# CIBLE_Main.net
KiCad netlist of a schematic drawn in Altium Designer
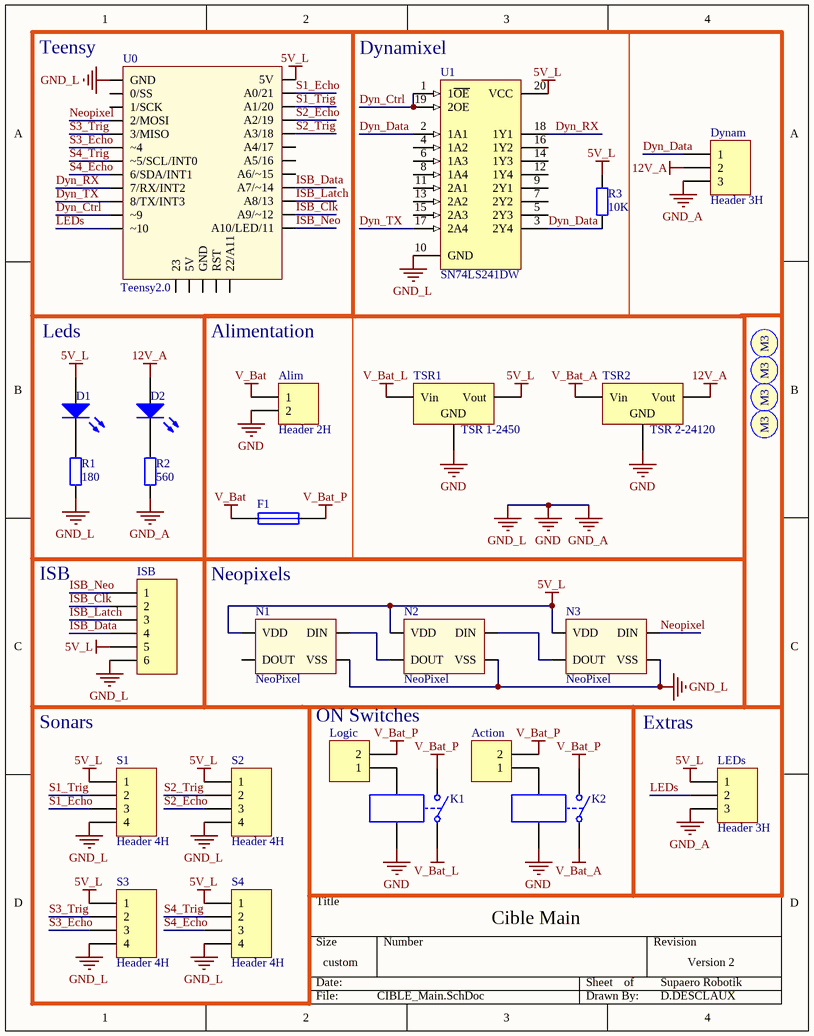
[diagram p0: CIBLE_Main.SchDoc]

(export (version "E")
  (design (tool "Eeschema 10.0.6"))
  (components
    (comp (ref "Action")
      (value "Action")
      (footprint "Molex SPOX 2x1H")
      (description "Header, 2-Pin, Right Angle")
      (fields (field (name "PUBLISHER") "Altium Limited"))
      (libsource (lib "Miscellaneous Connectors") (part "Header 2H"))
    )
    (comp (ref "Alim")
      (value "Header 2H")
      (footprint "Battery SALE")
      (description "Header, 2-Pin, Right Angle")
      (fields (field (name "PUBLISHER") "Altium Limited"))
      (libsource (lib "") (part "Header 2H_1"))
    )
    (comp (ref "D1")
      (value "KP-3216SEC")
      (footprint "3.2X1.6X1.1")
      (description "Typical RED, GREEN, YELLOW, AMBER GaAs LED")
      (fields (field (name "PUBLISHER") "Altium Limited"))
      (libsource (lib "Miscellaneous Devices") (part "LED2"))
    )
    (comp (ref "D2")
      (value "KP-3216SEC")
      (footprint "3.2X1.6X1.1")
      (description "Typical RED, GREEN, YELLOW, AMBER GaAs LED")
      (fields (field (name "PUBLISHER") "Altium Limited"))
      (libsource (lib "Miscellaneous Devices") (part "LED2"))
    )
    (comp (ref "Dynam")
      (value "Header 3H")
      (footprint "Molex SPOX 3x1H")
      (description "Header, 3-Pin, Right Angle")
      (fields (field (name "PUBLISHER") "Altium Limited"))
      (libsource (lib "Miscellaneous Connectors") (part "Header 3H"))
    )
    (comp (ref "F1")
      (value "Fuse 1")
      (footprint "Fuse")
      (description "Fuse")
      (fields (field (name "PUBLISHER") "Altium Limited"))
      (libsource (lib "Miscellaneous Devices") (part "Fuse 1"))
    )
    (comp (ref "ISB")
      (value "Header 6H")
      (footprint "MOLEX SPOX 6X1H")
      (description "Header, 6-Pin, Right Angle")
      (fields (field (name "PUBLISHER") "Altium Limited"))
      (libsource (lib "Miscellaneous Connectors") (part "Header 6H"))
    )
    (comp (ref "K1")
      (value "OJ-SS-112LMH2")
      (footprint "Relay")
      (description "Single-Pole Single-Throw Relay")
      (fields (field (name "PUBLISHER") "Altium Limited"))
      (libsource (lib "Miscellaneous Devices") (part "Relay-SPST"))
    )
    (comp (ref "K2")
      (value "OJ-SS-112LMH2")
      (footprint "Relay")
      (description "Single-Pole Single-Throw Relay")
      (fields (field (name "PUBLISHER") "Altium Limited"))
      (libsource (lib "Miscellaneous Devices") (part "Relay-SPST"))
    )
    (comp (ref "LEDs")
      (value "Header 3H")
      (footprint "Molex SPOX 3x1H")
      (description "Header, 3-Pin, Right Angle")
      (fields (field (name "PUBLISHER") "Altium Limited"))
      (libsource (lib "Miscellaneous Connectors") (part "Header 3H"))
    )
    (comp (ref "Logic")
      (value "Logic")
      (footprint "Molex SPOX 2x1H")
      (description "Header, 2-Pin, Right Angle")
      (fields (field (name "PUBLISHER") "Altium Limited"))
      (libsource (lib "Miscellaneous Connectors") (part "Header 2H"))
    )
    (comp (ref "N1")
      (value "NeoPixel")
      (footprint "Robot_2019:Neopixel")
      (libsource (lib "Robot_2019") (part "NeoPixel"))
    )
    (comp (ref "N2")
      (value "NeoPixel")
      (footprint "Robot_2019:Neopixel")
      (libsource (lib "Robot_2019") (part "NeoPixel"))
    )
    (comp (ref "N3")
      (value "NeoPixel")
      (footprint "Robot_2019:Neopixel")
      (libsource (lib "Robot_2019") (part "NeoPixel"))
    )
    (comp (ref "R1")
      (value "180")
      (footprint "3.2X1.6X1.1")
      (description "Resistor")
      (fields (field (name "Comment") "Res2") (field (name "PUBLISHER") "Altium Limited"))
      (libsource (lib "Miscellaneous Devices") (part "Res2"))
    )
    (comp (ref "R2")
      (value "560")
      (footprint "3.2X1.6X1.1")
      (description "Resistor")
      (fields (field (name "Comment") "Res2") (field (name "PUBLISHER") "Altium Limited"))
      (libsource (lib "Miscellaneous Devices") (part "Res2"))
    )
    (comp (ref "R3")
      (value "10K")
      (footprint "3.2X1.6X1.1")
      (description "Resistor")
      (fields (field (name "Comment") "Res2") (field (name "PUBLISHER") "Altium Limited"))
      (libsource (lib "") (part "Res2_1"))
    )
    (comp (ref "S1")
      (value "Header 4H")
      (footprint "Molex SPOX 4x1H")
      (description "Header, 4-Pin, Right Angle")
      (fields (field (name "PUBLISHER") "Altium Limited"))
      (libsource (lib "Miscellaneous Connectors") (part "Header 4H"))
    )
    (comp (ref "S2")
      (value "Header 4H")
      (footprint "Molex SPOX 4x1H")
      (description "Header, 4-Pin, Right Angle")
      (fields (field (name "PUBLISHER") "Altium Limited"))
      (libsource (lib "Miscellaneous Connectors") (part "Header 4H"))
    )
    (comp (ref "S3")
      (value "Header 4H")
      (footprint "Molex SPOX 4x1H")
      (description "Header, 4-Pin, Right Angle")
      (fields (field (name "PUBLISHER") "Altium Limited"))
      (libsource (lib "Miscellaneous Connectors") (part "Header 4H"))
    )
    (comp (ref "S4")
      (value "Header 4H")
      (footprint "Molex SPOX 4x1H")
      (description "Header, 4-Pin, Right Angle")
      (fields (field (name "PUBLISHER") "Altium Limited"))
      (libsource (lib "Miscellaneous Connectors") (part "Header 4H"))
    )
    (comp (ref "SC1")
      (value "Screw M3")
      (footprint "Robot_2019:Screw M3")
      (libsource (lib "Robot_2019") (part "Screw M3"))
    )
    (comp (ref "SC2")
      (value "Screw M3")
      (footprint "Robot_2019:Screw M3")
      (libsource (lib "Robot_2019") (part "Screw M3"))
    )
    (comp (ref "SC3")
      (value "Screw M3")
      (footprint "Robot_2019:Screw M3")
      (libsource (lib "Robot_2019") (part "Screw M3"))
    )
    (comp (ref "SC4")
      (value "Screw M3")
      (footprint "Robot_2019:Screw M3")
      (libsource (lib "Robot_2019") (part "Screw M3"))
    )
    (comp (ref "TSR1")
      (value "TSR 1-2450")
      (footprint "TRS")
      (description "Voltage Regulator")
      (fields (field (name "PUBLISHER") "Altium Limited"))
      (libsource (lib "Miscellaneous Devices") (part "Volt Reg"))
    )
    (comp (ref "TSR2")
      (value "TSR 2-24120")
      (footprint "TRS - centered")
      (description "Voltage Regulator")
      (fields (field (name "PUBLISHER") "Altium Limited"))
      (libsource (lib "Miscellaneous Devices") (part "Volt Reg"))
    )
    (comp (ref "U0")
      (value "Teensy2.0")
      (footprint "Teensy2.0")
      (description "Teensy 2.0 with minimal pinout")
      (libsource (lib "Robot_2019") (part "Teensy2.0"))
    )
    (comp (ref "U1")
      (value "SN74LS241DW")
      (footprint "DW020_N")
      (description "Octal Buffer and Line Driver with 3-State Outputs")
      (fields (field (name "PUBLISHER") "Altium Limited"))
      (libsource (lib "TI Logic Buffer Line Driver") (part "SN74LS241DW"))
    )
  )
  (nets
    (net (code "1") (name "/Dyn_Ctrl") (class "Default")
      (node (ref "U0") (pin "11") (pinfunction "~9_11") (pintype "passive"))
      (node (ref "U1") (pin "1") (pinfunction "1~{OE}_1") (pintype "input"))
      (node (ref "U1") (pin "19") (pinfunction "2OE_19") (pintype "input"))
    )
    (net (code "2") (name "/Dyn_Data") (class "Default")
      (node (ref "Dynam") (pin "1") (pinfunction "1_1") (pintype "passive"))
      (node (ref "R3") (pin "1") (pinfunction "1_1") (pintype "passive"))
      (node (ref "U1") (pin "2") (pinfunction "1A1_2") (pintype "input"))
      (node (ref "U1") (pin "3") (pinfunction "2Y4_3") (pintype "tri_state"))
    )
    (net (code "3") (name "/Dyn_RX") (class "Default")
      (node (ref "U0") (pin "9") (pinfunction "7/RX/INT2_9") (pintype "passive"))
      (node (ref "U1") (pin "18") (pinfunction "1Y1_18") (pintype "tri_state"))
    )
    (net (code "4") (name "/Dyn_TX") (class "Default")
      (node (ref "U0") (pin "10") (pinfunction "8/TX/INT3_10") (pintype "passive"))
      (node (ref "U1") (pin "17") (pinfunction "2A4_17") (pintype "input"))
    )
    (net (code "5") (name "/ISB_Clk") (class "Default")
      (node (ref "ISB") (pin "2") (pinfunction "2_2") (pintype "passive"))
      (node (ref "U0") (pin "19") (pinfunction "A9/~12_19") (pintype "passive"))
    )
    (net (code "6") (name "/ISB_Data") (class "Default")
      (node (ref "ISB") (pin "4") (pinfunction "4_4") (pintype "passive"))
      (node (ref "U0") (pin "21") (pinfunction "A7/~14_21") (pintype "passive"))
    )
    (net (code "7") (name "/ISB_Latch") (class "Default")
      (node (ref "ISB") (pin "3") (pinfunction "3_3") (pintype "passive"))
      (node (ref "U0") (pin "20") (pinfunction "A8/13_20") (pintype "passive"))
    )
    (net (code "8") (name "/ISB_Neo") (class "Default")
      (node (ref "ISB") (pin "1") (pinfunction "1_1") (pintype "passive"))
      (node (ref "U0") (pin "18") (pinfunction "A10/LED/11_18") (pintype "passive"))
    )
    (net (code "9") (name "/LEDs") (class "Default")
      (node (ref "LEDs") (pin "2") (pinfunction "2_2") (pintype "passive"))
      (node (ref "U0") (pin "12") (pinfunction "~10_12") (pintype "passive"))
    )
    (net (code "10") (name "/Neopixel") (class "Default")
      (node (ref "N3") (pin "3") (pinfunction "DIN_3") (pintype "passive"))
      (node (ref "U0") (pin "4") (pinfunction "2/MOSI_4") (pintype "passive"))
    )
    (net (code "11") (name "/S1_Echo") (class "Default")
      (node (ref "S1") (pin "3") (pinfunction "3_3") (pintype "passive"))
      (node (ref "U0") (pin "28") (pinfunction "A0/21_28") (pintype "passive"))
    )
    (net (code "12") (name "/S1_Trig") (class "Default")
      (node (ref "S1") (pin "2") (pinfunction "2_2") (pintype "passive"))
      (node (ref "U0") (pin "27") (pinfunction "A1/20_27") (pintype "passive"))
    )
    (net (code "13") (name "/S2_Echo") (class "Default")
      (node (ref "S2") (pin "3") (pinfunction "3_3") (pintype "passive"))
      (node (ref "U0") (pin "26") (pinfunction "A2/19_26") (pintype "passive"))
    )
    (net (code "14") (name "/S2_Trig") (class "Default")
      (node (ref "S2") (pin "2") (pinfunction "2_2") (pintype "passive"))
      (node (ref "U0") (pin "25") (pinfunction "A3/18_25") (pintype "passive"))
    )
    (net (code "15") (name "/S3_Echo") (class "Default")
      (node (ref "S3") (pin "3") (pinfunction "3_3") (pintype "passive"))
      (node (ref "U0") (pin "6") (pinfunction "~4_6") (pintype "passive"))
    )
    (net (code "16") (name "/S3_Trig") (class "Default")
      (node (ref "S3") (pin "2") (pinfunction "2_2") (pintype "passive"))
      (node (ref "U0") (pin "5") (pinfunction "3/MISO_5") (pintype "passive"))
    )
    (net (code "17") (name "/S4_Echo") (class "Default")
      (node (ref "S4") (pin "3") (pinfunction "3_3") (pintype "passive"))
      (node (ref "U0") (pin "8") (pinfunction "6/SDA/INT1_8") (pintype "passive"))
    )
    (net (code "18") (name "/S4_Trig") (class "Default")
      (node (ref "S4") (pin "2") (pinfunction "2_2") (pintype "passive"))
      (node (ref "U0") (pin "7") (pinfunction "~5/SCL/INT0_7") (pintype "passive"))
    )
    (net (code "19") (name "5V_L") (class "Default")
      (node (ref "D1") (pin "1") (pinfunction "A_1") (pintype "passive"))
      (node (ref "ISB") (pin "5") (pinfunction "5_5") (pintype "passive"))
      (node (ref "LEDs") (pin "1") (pinfunction "1_1") (pintype "passive"))
      (node (ref "N1") (pin "4") (pinfunction "VDD_4") (pintype "passive"))
      (node (ref "N2") (pin "4") (pinfunction "VDD_4") (pintype "passive"))
      (node (ref "N3") (pin "4") (pinfunction "VDD_4") (pintype "passive"))
      (node (ref "R3") (pin "2") (pinfunction "2_2") (pintype "passive"))
      (node (ref "S1") (pin "1") (pinfunction "1_1") (pintype "passive"))
      (node (ref "S2") (pin "1") (pinfunction "1_1") (pintype "passive"))
      (node (ref "S3") (pin "1") (pinfunction "1_1") (pintype "passive"))
      (node (ref "S4") (pin "1") (pinfunction "1_1") (pintype "passive"))
      (node (ref "TSR1") (pin "3") (pinfunction "Vout_3") (pintype "passive"))
      (node (ref "U0") (pin "29") (pinfunction "5V_29") (pintype "passive"))
      (node (ref "U1") (pin "20") (pinfunction "VCC_20") (pintype "power_in"))
    )
    (net (code "20") (name "12V_A") (class "Default")
      (node (ref "D2") (pin "1") (pinfunction "A_1") (pintype "passive"))
      (node (ref "Dynam") (pin "2") (pinfunction "2_2") (pintype "passive"))
      (node (ref "TSR2") (pin "3") (pinfunction "Vout_3") (pintype "passive"))
    )
    (net (code "21") (name "GND") (class "Default")
      (node (ref "Alim") (pin "2") (pinfunction "2_2") (pintype "passive"))
      (node (ref "Dynam") (pin "3") (pinfunction "3_3") (pintype "passive"))
      (node (ref "ISB") (pin "6") (pinfunction "6_6") (pintype "passive"))
      (node (ref "K1") (pin "3") (pinfunction "3_3") (pintype "passive"))
      (node (ref "K2") (pin "3") (pinfunction "3_3") (pintype "passive"))
      (node (ref "LEDs") (pin "3") (pinfunction "3_3") (pintype "passive"))
      (node (ref "N1") (pin "2") (pinfunction "VSS_2") (pintype "passive"))
      (node (ref "N2") (pin "2") (pinfunction "VSS_2") (pintype "passive"))
      (node (ref "N3") (pin "2") (pinfunction "VSS_2") (pintype "passive"))
      (node (ref "R1") (pin "2") (pinfunction "2_2") (pintype "passive"))
      (node (ref "R2") (pin "2") (pinfunction "2_2") (pintype "passive"))
      (node (ref "S1") (pin "4") (pinfunction "4_4") (pintype "passive"))
      (node (ref "S2") (pin "4") (pinfunction "4_4") (pintype "passive"))
      (node (ref "S3") (pin "4") (pinfunction "4_4") (pintype "passive"))
      (node (ref "S4") (pin "4") (pinfunction "4_4") (pintype "passive"))
      (node (ref "TSR1") (pin "2") (pinfunction "GND_2") (pintype "passive"))
      (node (ref "TSR2") (pin "2") (pinfunction "GND_2") (pintype "passive"))
      (node (ref "U0") (pin "1") (pinfunction "GND_1") (pintype "passive"))
      (node (ref "U1") (pin "10") (pinfunction "GND_10") (pintype "power_in"))
    )
    (net (code "22") (name "Net-(Action-Pad1)") (class "Default")
      (node (ref "Action") (pin "1") (pinfunction "1_1") (pintype "passive"))
      (node (ref "K2") (pin "4") (pinfunction "4_4") (pintype "passive"))
    )
    (net (code "23") (name "Net-(D1-K)") (class "Default")
      (node (ref "D1") (pin "2") (pinfunction "K_2") (pintype "passive"))
      (node (ref "R1") (pin "1") (pinfunction "1_1") (pintype "passive"))
    )
    (net (code "24") (name "Net-(D2-K)") (class "Default")
      (node (ref "D2") (pin "2") (pinfunction "K_2") (pintype "passive"))
      (node (ref "R2") (pin "1") (pinfunction "1_1") (pintype "passive"))
    )
    (net (code "25") (name "Net-(K1-Pad4)") (class "Default")
      (node (ref "K1") (pin "4") (pinfunction "4_4") (pintype "passive"))
      (node (ref "Logic") (pin "1") (pinfunction "1_1") (pintype "passive"))
    )
    (net (code "26") (name "Net-(N1-DIN)") (class "Default")
      (node (ref "N1") (pin "3") (pinfunction "DIN_3") (pintype "passive"))
      (node (ref "N2") (pin "1") (pinfunction "DOUT_1") (pintype "passive"))
    )
    (net (code "27") (name "Net-(N2-DIN)") (class "Default")
      (node (ref "N2") (pin "3") (pinfunction "DIN_3") (pintype "passive"))
      (node (ref "N3") (pin "1") (pinfunction "DOUT_1") (pintype "passive"))
    )
    (net (code "28") (name "V_Bat") (class "Default")
      (node (ref "Alim") (pin "1") (pinfunction "1_1") (pintype "passive"))
      (node (ref "F1") (pin "1") (pinfunction "1_1") (pintype "passive"))
    )
    (net (code "29") (name "V_Bat_A") (class "Default")
      (node (ref "K2") (pin "1") (pinfunction "1_1") (pintype "passive"))
      (node (ref "TSR2") (pin "1") (pinfunction "Vin_1") (pintype "passive"))
    )
    (net (code "30") (name "V_Bat_L") (class "Default")
      (node (ref "K1") (pin "1") (pinfunction "1_1") (pintype "passive"))
      (node (ref "TSR1") (pin "1") (pinfunction "Vin_1") (pintype "passive"))
    )
    (net (code "31") (name "V_Bat_P") (class "Default")
      (node (ref "Action") (pin "2") (pinfunction "2_2") (pintype "passive"))
      (node (ref "F1") (pin "2") (pinfunction "2_2") (pintype "passive"))
      (node (ref "K1") (pin "2") (pinfunction "2_2") (pintype "passive"))
      (node (ref "K2") (pin "2") (pinfunction "2_2") (pintype "passive"))
      (node (ref "Logic") (pin "2") (pinfunction "2_2") (pintype "passive"))
    )
    (net (code "32") (name "unconnected-(N1-DOUT-Pad1)") (class "Default")
      (node (ref "N1") (pin "1") (pinfunction "DOUT_1") (pintype "passive"))
    )
    (net (code "33") (name "unconnected-(U0-0{slash}SS-Pad2)") (class "Default")
      (node (ref "U0") (pin "2") (pinfunction "0/SS_2") (pintype "passive"))
    )
    (net (code "34") (name "unconnected-(U0-1{slash}SCK-Pad3)") (class "Default")
      (node (ref "U0") (pin "3") (pinfunction "1/SCK_3") (pintype "passive"))
    )
    (net (code "35") (name "unconnected-(U0-5V-Pad14)") (class "Default")
      (node (ref "U0") (pin "14") (pinfunction "5V_14") (pintype "passive"))
    )
    (net (code "36") (name "unconnected-(U0-22{slash}A11-Pad17)") (class "Default")
      (node (ref "U0") (pin "17") (pinfunction "22/A11_17") (pintype "passive"))
    )
    (net (code "37") (name "unconnected-(U0-23-Pad13)") (class "Default")
      (node (ref "U0") (pin "13") (pinfunction "23_13") (pintype "passive"))
    )
    (net (code "38") (name "unconnected-(U0-A4{slash}17-Pad24)") (class "Default")
      (node (ref "U0") (pin "24") (pinfunction "A4/17_24") (pintype "passive"))
    )
    (net (code "39") (name "unconnected-(U0-A5{slash}16-Pad23)") (class "Default")
      (node (ref "U0") (pin "23") (pinfunction "A5/16_23") (pintype "passive"))
    )
    (net (code "40") (name "unconnected-(U0-A6{slash}~15-Pad22)") (class "Default")
      (node (ref "U0") (pin "22") (pinfunction "A6/~15_22") (pintype "passive"))
    )
    (net (code "41") (name "unconnected-(U0-GND-Pad15)") (class "Default")
      (node (ref "U0") (pin "15") (pinfunction "GND_15") (pintype "passive"))
    )
    (net (code "42") (name "unconnected-(U0-RST-Pad16)") (class "Default")
      (node (ref "U0") (pin "16") (pinfunction "RST_16") (pintype "passive"))
    )
    (net (code "43") (name "unconnected-(U1-1A2-Pad4)") (class "Default")
      (node (ref "U1") (pin "4") (pinfunction "1A2_4") (pintype "input"))
    )
    (net (code "44") (name "unconnected-(U1-1A3-Pad6)") (class "Default")
      (node (ref "U1") (pin "6") (pinfunction "1A3_6") (pintype "input"))
    )
    (net (code "45") (name "unconnected-(U1-1A4-Pad8)") (class "Default")
      (node (ref "U1") (pin "8") (pinfunction "1A4_8") (pintype "input"))
    )
    (net (code "46") (name "unconnected-(U1-1Y2-Pad16)") (class "Default")
      (node (ref "U1") (pin "16") (pinfunction "1Y2_16") (pintype "tri_state"))
    )
    (net (code "47") (name "unconnected-(U1-1Y3-Pad14)") (class "Default")
      (node (ref "U1") (pin "14") (pinfunction "1Y3_14") (pintype "tri_state"))
    )
    (net (code "48") (name "unconnected-(U1-1Y4-Pad12)") (class "Default")
      (node (ref "U1") (pin "12") (pinfunction "1Y4_12") (pintype "tri_state"))
    )
    (net (code "49") (name "unconnected-(U1-2A1-Pad11)") (class "Default")
      (node (ref "U1") (pin "11") (pinfunction "2A1_11") (pintype "input"))
    )
    (net (code "50") (name "unconnected-(U1-2A2-Pad13)") (class "Default")
      (node (ref "U1") (pin "13") (pinfunction "2A2_13") (pintype "input"))
    )
    (net (code "51") (name "unconnected-(U1-2A3-Pad15)") (class "Default")
      (node (ref "U1") (pin "15") (pinfunction "2A3_15") (pintype "input"))
    )
    (net (code "52") (name "unconnected-(U1-2Y1-Pad9)") (class "Default")
      (node (ref "U1") (pin "9") (pinfunction "2Y1_9") (pintype "tri_state"))
    )
    (net (code "53") (name "unconnected-(U1-2Y2-Pad7)") (class "Default")
      (node (ref "U1") (pin "7") (pinfunction "2Y2_7") (pintype "tri_state"))
    )
    (net (code "54") (name "unconnected-(U1-2Y3-Pad5)") (class "Default")
      (node (ref "U1") (pin "5") (pinfunction "2Y3_5") (pintype "tri_state"))
    )
  )
)
